# BOOT_JTAG_AUX.net
KiCad netlist of a schematic drawn in Altium Designer
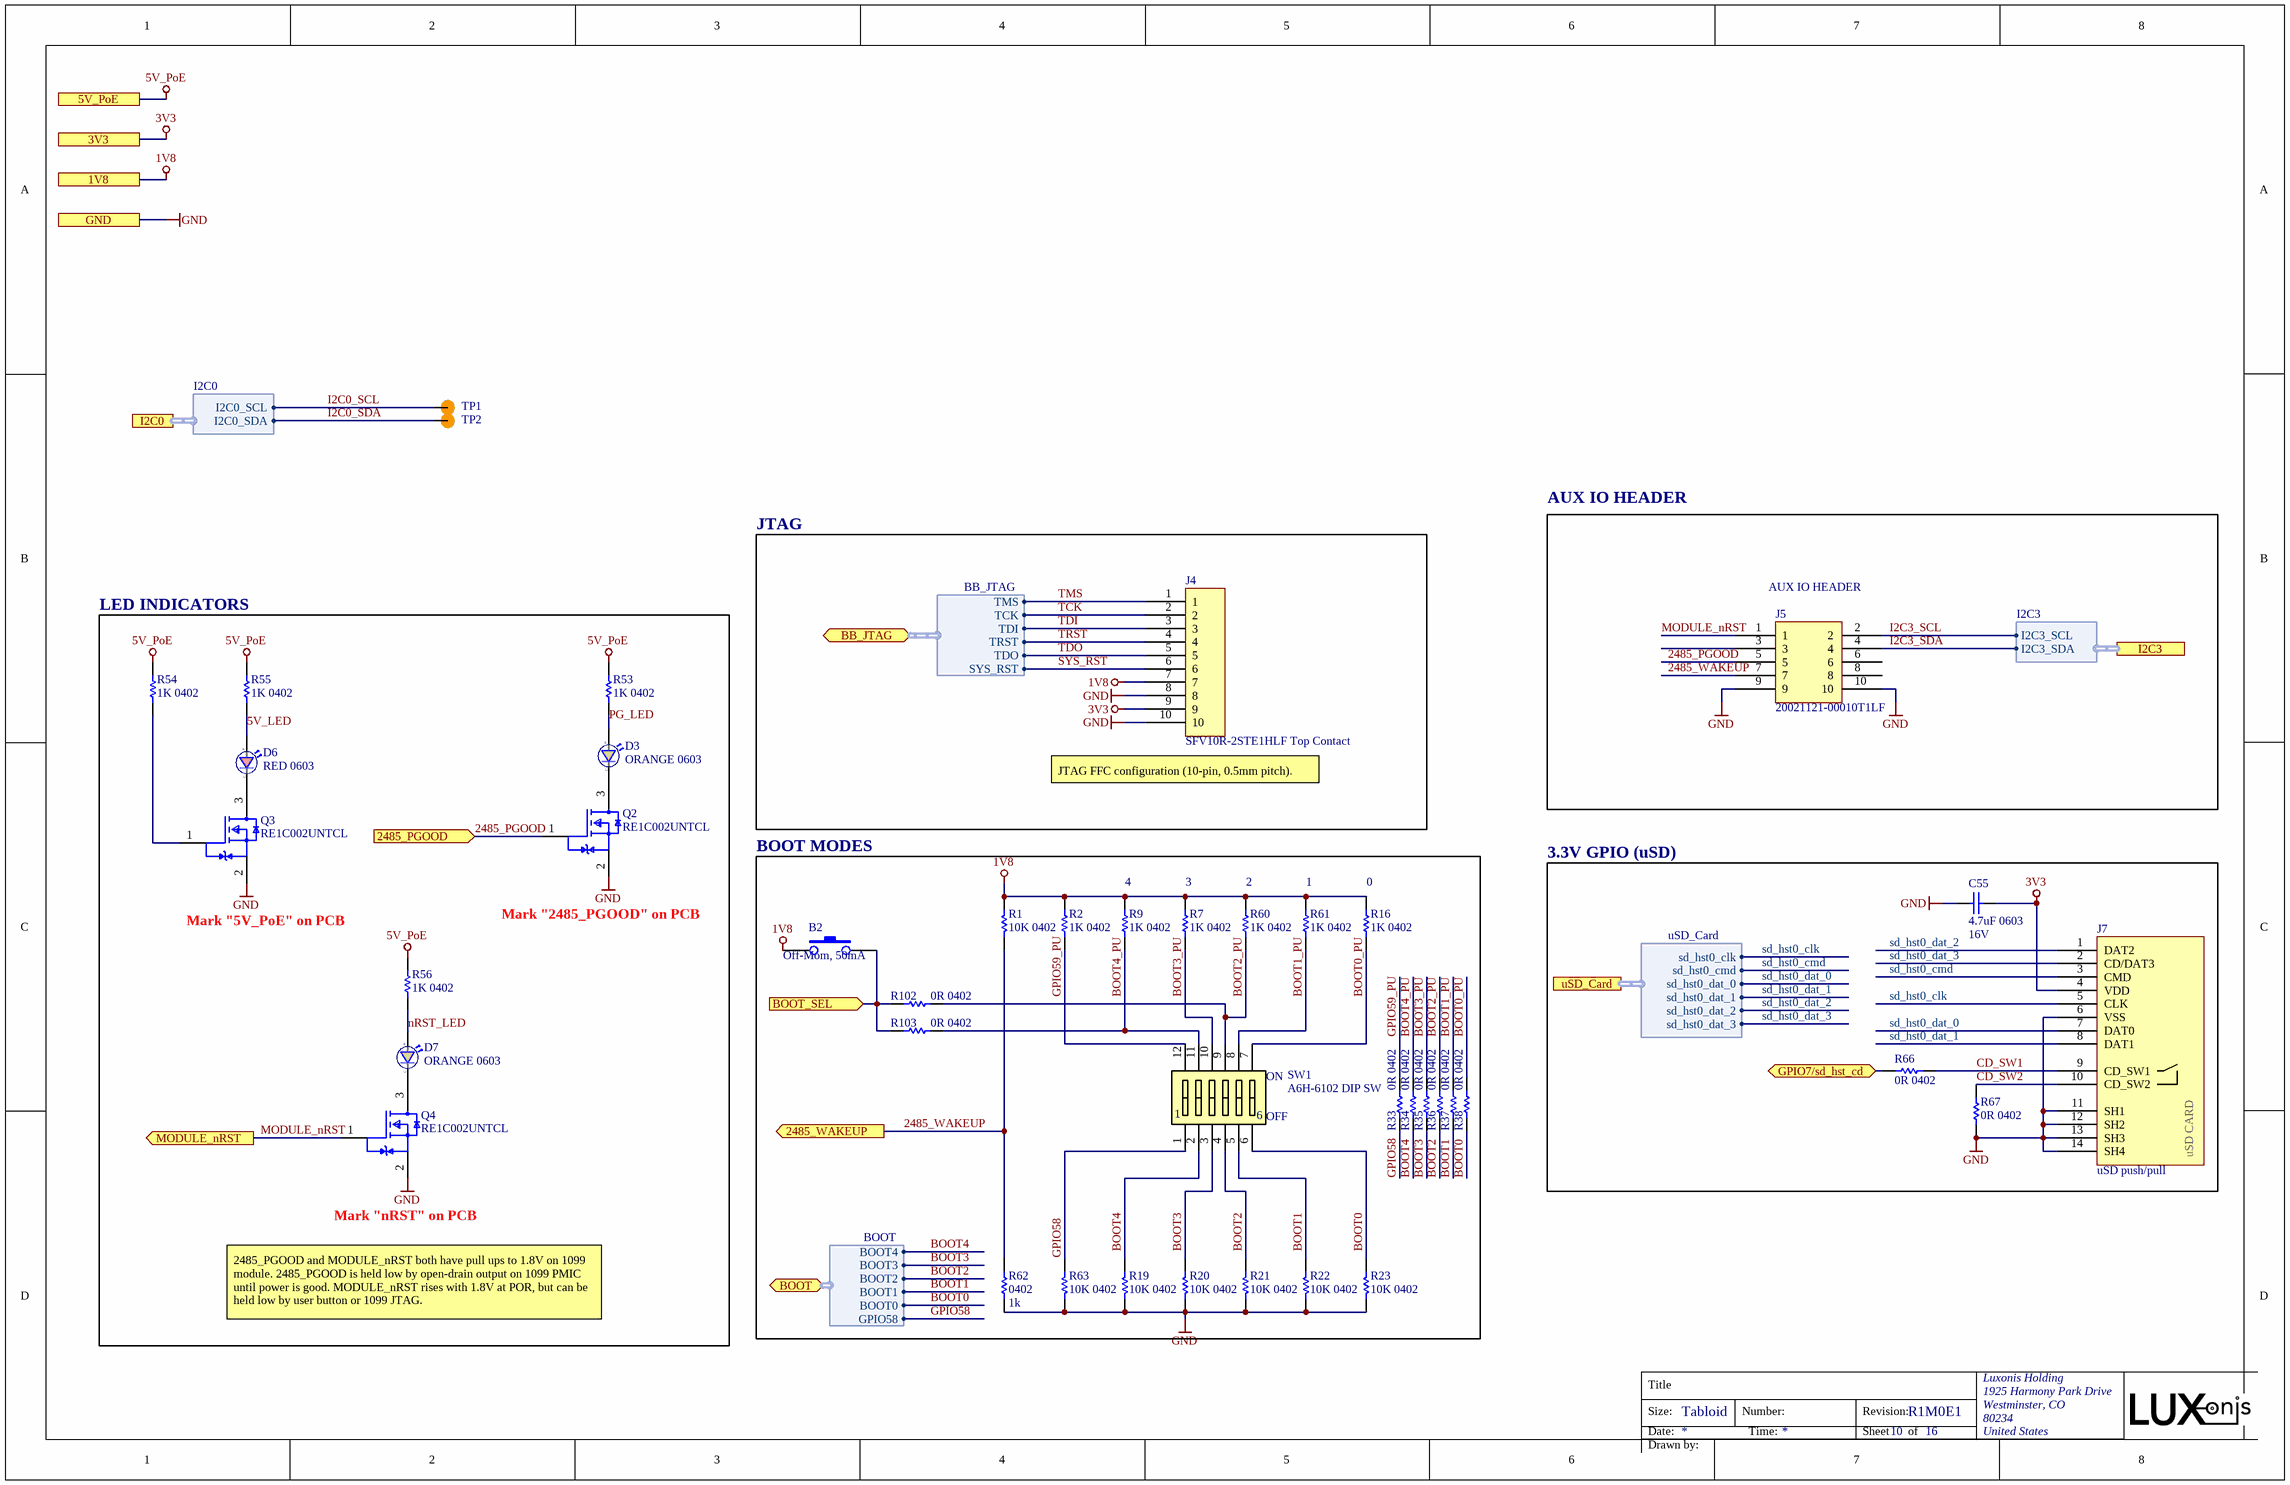
[diagram p0: BOOT_JTAG_AUX.SchDoc]

(export (version "E")
  (design (tool "Eeschema 10.0.6"))
  (components
    (comp (ref "B2")
      (value "Off-Mom, 50mA")
      (footprint "LuxonisMaster:DTSM-32N-V")
      (description "SWITCH TACTILE SMT 3.5mm * 6mm , brown 160gf")
      (libsource (lib "LuxonisMaster") (part "DTSM-32N-V"))
    )
    (comp (ref "C55")
      (value "4.7uF 0603")
      (footprint "CAPC0603(1608)100_N")
      (description "CAP CER 4.7UF 16V X5R 0603 10%")
      (fields (field (name "TOLERANCE") "10%") (field (name "VOLTAGE RATING") "16V"))
      (libsource (lib "LuxonisMaster") (part "GRM188R61C475KAAJD"))
    )
    (comp (ref "D3")
      (value "ORANGE 0603")
      (footprint "LuxonisMaster:SML_D1xx8W")
      (description "LED ORANGE DIFFUSED 0603 SMD Orange 605nm LED Indication - Discrete 2.2V 0603 (1608 Metric)")
      (libsource (lib "LuxonisMaster") (part "SML-D12D8WT86"))
    )
    (comp (ref "D6")
      (value "RED 0603")
      (footprint "LuxonisMaster:SML_D1xx8W")
      (description "LED RED DIFFUSED 0603 SMD Red 620nm LED Indication - Discrete 2.2V 0603 (1608 Metric)")
      (libsource (lib "LuxonisMaster") (part "SML-D12U8WT86"))
    )
    (comp (ref "D7")
      (value "ORANGE 0603")
      (footprint "LuxonisMaster:SML_D1xx8W")
      (description "LED ORANGE DIFFUSED 0603 SMD Orange 605nm LED Indication - Discrete 2.2V 0603 (1608 Metric)")
      (libsource (lib "LuxonisMaster") (part "SML-D12D8WT86"))
    )
    (comp (ref "J4")
      (value "SFV10R-2STE1HLF Top Contact")
      (footprint "LuxonisMaster:SFV10R-2STE1HLF")
      (description "CONN FFC TOP 10POS 0.50MM R/A")
      (libsource (lib "LuxonisMaster") (part "SFV10R-2STE1HLF"))
    )
    (comp (ref "J5")
      (value "20021121-00010T1LF")
      (footprint "LuxonisMaster:20021121-00010T1LF")
      (description "CONN HEADER SMD 10POS 1.27MM")
      (libsource (lib "LuxonisMaster") (part "20021121-00010T1LF"))
    )
    (comp (ref "J7")
      (value "uSD push/pull")
      (footprint "LuxonisMaster:104031-0811")
      (description "CONN MICRO SD CARD PUSH-PULL R/A")
      (libsource (lib "LuxonisMaster") (part "104031-0811"))
    )
    (comp (ref "Q2")
      (value "RE1C002UNTCL")
      (footprint "LuxonisMaster:RE1C002UNTCL")
      (description "MOSFET N-CH 20V 0.2A EMT3")
      (libsource (lib "LuxonisMaster") (part "RE1C002UNTCL"))
    )
    (comp (ref "Q3")
      (value "RE1C002UNTCL")
      (footprint "LuxonisMaster:RE1C002UNTCL")
      (description "MOSFET N-CH 20V 0.2A EMT3")
      (libsource (lib "LuxonisMaster") (part "RE1C002UNTCL"))
    )
    (comp (ref "Q4")
      (value "RE1C002UNTCL")
      (footprint "LuxonisMaster:RE1C002UNTCL")
      (description "MOSFET N-CH 20V 0.2A EMT3")
      (libsource (lib "LuxonisMaster") (part "RE1C002UNTCL"))
    )
    (comp (ref "R1")
      (value "10K 0402")
      (footprint "RESC0402(1005)_N")
      (fields (field (name "TOLERANCE") "1%"))
      (libsource (lib "LuxonisMaster") (part "RC0402FR-1310KL"))
    )
    (comp (ref "R2")
      (value "1K 0402")
      (footprint "RESC0402(1005)_N")
      (fields (field (name "TOLERANCE") "1%"))
      (libsource (lib "LuxonisMaster") (part "RC0402FR-071KL"))
    )
    (comp (ref "R7")
      (value "1K 0402")
      (footprint "RESC0402(1005)_N")
      (fields (field (name "TOLERANCE") "1%"))
      (libsource (lib "LuxonisMaster") (part "RC0402FR-071KL"))
    )
    (comp (ref "R9")
      (value "1K 0402")
      (footprint "RESC0402(1005)_N")
      (fields (field (name "TOLERANCE") "1%"))
      (libsource (lib "LuxonisMaster") (part "RC0402FR-071KL"))
    )
    (comp (ref "R16")
      (value "1K 0402")
      (footprint "RESC0402(1005)_N")
      (fields (field (name "TOLERANCE") "1%"))
      (libsource (lib "LuxonisMaster") (part "RC0402FR-071KL"))
    )
    (comp (ref "R19")
      (value "10K 0402")
      (footprint "RESC0402(1005)_N")
      (fields (field (name "TOLERANCE") "1%"))
      (libsource (lib "LuxonisMaster") (part "RC0402FR-1310KL"))
    )
    (comp (ref "R20")
      (value "10K 0402")
      (footprint "RESC0402(1005)_N")
      (fields (field (name "TOLERANCE") "1%"))
      (libsource (lib "LuxonisMaster") (part "RC0402FR-1310KL"))
    )
    (comp (ref "R21")
      (value "10K 0402")
      (footprint "RESC0402(1005)_N")
      (fields (field (name "TOLERANCE") "1%"))
      (libsource (lib "LuxonisMaster") (part "RC0402FR-1310KL"))
    )
    (comp (ref "R22")
      (value "10K 0402")
      (footprint "RESC0402(1005)_N")
      (fields (field (name "TOLERANCE") "1%"))
      (libsource (lib "LuxonisMaster") (part "RC0402FR-1310KL"))
    )
    (comp (ref "R23")
      (value "10K 0402")
      (footprint "RESC0402(1005)_N")
      (fields (field (name "TOLERANCE") "1%"))
      (libsource (lib "LuxonisMaster") (part "RC0402FR-1310KL"))
    )
    (comp (ref "R33")
      (value "0R 0402")
      (footprint "RES_Altium_Vault_Generic:RESC0402(1005)_L")
      (description "RES SMD 0 OHM JUMPER 1/16W 0402")
      (fields (field (name "TOLERANCE") "5%"))
      (libsource (lib "LuxonisMaster") (part "CRCW04020000Z0ED"))
    )
    (comp (ref "R34")
      (value "0R 0402")
      (footprint "RES_Altium_Vault_Generic:RESC0402(1005)_L")
      (description "RES SMD 0 OHM JUMPER 1/16W 0402")
      (fields (field (name "TOLERANCE") "5%"))
      (libsource (lib "LuxonisMaster") (part "CRCW04020000Z0ED"))
    )
    (comp (ref "R35")
      (value "0R 0402")
      (footprint "RES_Altium_Vault_Generic:RESC0402(1005)_L")
      (description "RES SMD 0 OHM JUMPER 1/16W 0402")
      (fields (field (name "TOLERANCE") "5%"))
      (libsource (lib "LuxonisMaster") (part "CRCW04020000Z0ED"))
    )
    (comp (ref "R36")
      (value "0R 0402")
      (footprint "RES_Altium_Vault_Generic:RESC0402(1005)_L")
      (description "RES SMD 0 OHM JUMPER 1/16W 0402")
      (fields (field (name "TOLERANCE") "5%"))
      (libsource (lib "LuxonisMaster") (part "CRCW04020000Z0ED"))
    )
    (comp (ref "R37")
      (value "0R 0402")
      (footprint "RES_Altium_Vault_Generic:RESC0402(1005)_L")
      (description "RES SMD 0 OHM JUMPER 1/16W 0402")
      (fields (field (name "TOLERANCE") "5%"))
      (libsource (lib "LuxonisMaster") (part "CRCW04020000Z0ED"))
    )
    (comp (ref "R38")
      (value "0R 0402")
      (footprint "RES_Altium_Vault_Generic:RESC0402(1005)_L")
      (description "RES SMD 0 OHM JUMPER 1/16W 0402")
      (fields (field (name "TOLERANCE") "5%"))
      (libsource (lib "LuxonisMaster") (part "CRCW04020000Z0ED"))
    )
    (comp (ref "R53")
      (value "1K 0402")
      (footprint "RESC0402(1005)_N")
      (fields (field (name "TOLERANCE") "1%"))
      (libsource (lib "LuxonisMaster") (part "RC0402FR-071KL"))
    )
    (comp (ref "R54")
      (value "1K 0402")
      (footprint "RESC0402(1005)_N")
      (fields (field (name "TOLERANCE") "1%"))
      (libsource (lib "LuxonisMaster") (part "RC0402FR-071KL"))
    )
    (comp (ref "R55")
      (value "1K 0402")
      (footprint "RESC0402(1005)_N")
      (fields (field (name "TOLERANCE") "1%"))
      (libsource (lib "LuxonisMaster") (part "RC0402FR-071KL"))
    )
    (comp (ref "R56")
      (value "1K 0402")
      (footprint "RESC0402(1005)_N")
      (fields (field (name "TOLERANCE") "1%"))
      (libsource (lib "LuxonisMaster") (part "RC0402FR-071KL"))
    )
    (comp (ref "R60")
      (value "1K 0402")
      (footprint "RESC0402(1005)_N")
      (fields (field (name "TOLERANCE") "1%"))
      (libsource (lib "LuxonisMaster") (part "RC0402FR-071KL"))
    )
    (comp (ref "R61")
      (value "1K 0402")
      (footprint "RESC0402(1005)_N")
      (fields (field (name "TOLERANCE") "1%"))
      (libsource (lib "LuxonisMaster") (part "RC0402FR-071KL"))
    )
    (comp (ref "R62")
      (value "1k")
      (footprint "RESC0402(1005)_L")
      (description "RES SMD 1K OHM 1% 1/16W 0402")
      (fields
        (field (name "CASE/PACKAGE") "0402")
        (field (name "TOLERANCE") "1%")
        (field (name "Comment") "RC0402FR-071KL")
      )
      (libsource (lib "Luxonis LLC") (part "Default resistor symbol"))
    )
    (comp (ref "R63")
      (value "10K 0402")
      (footprint "RESC0402(1005)_N")
      (fields (field (name "TOLERANCE") "1%"))
      (libsource (lib "LuxonisMaster") (part "RC0402FR-1310KL"))
    )
    (comp (ref "R66")
      (value "0R 0402")
      (footprint "RESC0402(1005)_N")
      (description "RES SMD 0 OHM JUMPER 1/16W 0402")
      (fields (field (name "TOLERANCE") "5%"))
      (libsource (lib "LuxonisMaster") (part "CRCW04020000Z0ED"))
    )
    (comp (ref "R67")
      (value "0R 0402")
      (footprint "RESC0402(1005)_N")
      (description "RES SMD 0 OHM JUMPER 1/16W 0402")
      (fields (field (name "TOLERANCE") "5%"))
      (libsource (lib "LuxonisMaster") (part "CRCW04020000Z0ED"))
    )
    (comp (ref "R102")
      (value "0R 0402")
      (footprint "RES_Altium_Vault_Generic:RESC0402(1005)_L")
      (description "RES SMD 0 OHM JUMPER 1/16W 0402")
      (fields (field (name "TOLERANCE") "5%"))
      (libsource (lib "LuxonisMaster") (part "CRCW04020000Z0ED"))
    )
    (comp (ref "R103")
      (value "0R 0402")
      (footprint "RES_Altium_Vault_Generic:RESC0402(1005)_L")
      (description "RES SMD 0 OHM JUMPER 1/16W 0402")
      (fields (field (name "TOLERANCE") "5%"))
      (libsource (lib "LuxonisMaster") (part "CRCW04020000Z0ED"))
    )
    (comp (ref "SW1")
      (value "A6H-6102 DIP SW")
      (footprint "LuxonisMaster:A6H-610x")
      (description "SWITCH SLIDE DIP SPST 25MA 24V (SEALED)")
      (libsource (lib "LuxonisMaster") (part "A6H-6102"))
    )
    (comp (ref "TP1")
      (value "TP100_200_NS")
      (footprint "TP100_200_NS")
      (libsource (lib "LuxonisMaster") (part "TEST_POINT"))
    )
    (comp (ref "TP2")
      (value "TP100_200_NS")
      (footprint "TP100_200_NS")
      (libsource (lib "LuxonisMaster") (part "TEST_POINT"))
    )
  )
  (nets
    (net (code "6") (name "/5V_LED") (class "Default")
      (node (ref "D6") (pin "2") (pinfunction "A_2") (pintype "passive"))
      (node (ref "R55") (pin "1") (pinfunction "1_1") (pintype "passive"))
    )
    (net (code "7") (name "/2485_PGOOD") (class "Default")
      (node (ref "J5") (pin "5") (pinfunction "5_5") (pintype "passive"))
      (node (ref "Q2") (pin "1") (pinfunction "Gate_1") (pintype "passive"))
    )
    (net (code "8") (name "/2485_WAKEUP") (class "Default")
      (node (ref "J5") (pin "7") (pinfunction "7_7") (pintype "passive"))
      (node (ref "R1") (pin "2") (pinfunction "2_2") (pintype "passive"))
      (node (ref "R62") (pin "2") (pinfunction "2_2") (pintype "passive"))
    )
    (net (code "9") (name "/BOOT0") (class "Default")
      (node (ref "R23") (pin "1") (pinfunction "1_1") (pintype "passive"))
      (node (ref "R38") (pin "2") (pinfunction "2_2") (pintype "passive"))
      (node (ref "SW1") (pin "6") (pinfunction "6_6") (pintype "passive"))
    )
    (net (code "10") (name "/BOOT0_PU") (class "Default")
      (node (ref "R16") (pin "1") (pinfunction "1_1") (pintype "passive"))
      (node (ref "R38") (pin "1") (pinfunction "1_1") (pintype "passive"))
      (node (ref "SW1") (pin "7") (pinfunction "7_7") (pintype "passive"))
    )
    (net (code "11") (name "/BOOT1") (class "Default")
      (node (ref "R22") (pin "1") (pinfunction "1_1") (pintype "passive"))
      (node (ref "R37") (pin "2") (pinfunction "2_2") (pintype "passive"))
      (node (ref "SW1") (pin "5") (pinfunction "5_5") (pintype "passive"))
    )
    (net (code "12") (name "/BOOT1_PU") (class "Default")
      (node (ref "R37") (pin "1") (pinfunction "1_1") (pintype "passive"))
      (node (ref "R61") (pin "1") (pinfunction "1_1") (pintype "passive"))
      (node (ref "SW1") (pin "8") (pinfunction "8_8") (pintype "passive"))
    )
    (net (code "13") (name "/BOOT2") (class "Default")
      (node (ref "R21") (pin "1") (pinfunction "1_1") (pintype "passive"))
      (node (ref "R36") (pin "2") (pinfunction "2_2") (pintype "passive"))
      (node (ref "SW1") (pin "4") (pinfunction "4_4") (pintype "passive"))
    )
    (net (code "14") (name "/BOOT2_PU") (class "Default")
      (node (ref "R102") (pin "1") (pinfunction "1_1") (pintype "passive"))
      (node (ref "R36") (pin "1") (pinfunction "1_1") (pintype "passive"))
      (node (ref "R60") (pin "1") (pinfunction "1_1") (pintype "passive"))
      (node (ref "SW1") (pin "9") (pinfunction "9_9") (pintype "passive"))
    )
    (net (code "15") (name "/BOOT3") (class "Default")
      (node (ref "R20") (pin "1") (pinfunction "1_1") (pintype "passive"))
      (node (ref "R35") (pin "2") (pinfunction "2_2") (pintype "passive"))
      (node (ref "SW1") (pin "3") (pinfunction "3_3") (pintype "passive"))
    )
    (net (code "16") (name "/BOOT3_PU") (class "Default")
      (node (ref "R35") (pin "1") (pinfunction "1_1") (pintype "passive"))
      (node (ref "R7") (pin "1") (pinfunction "1_1") (pintype "passive"))
      (node (ref "SW1") (pin "10") (pinfunction "10_10") (pintype "passive"))
    )
    (net (code "17") (name "/BOOT4") (class "Default")
      (node (ref "R19") (pin "1") (pinfunction "1_1") (pintype "passive"))
      (node (ref "R34") (pin "2") (pinfunction "2_2") (pintype "passive"))
      (node (ref "SW1") (pin "2") (pinfunction "2_2") (pintype "passive"))
    )
    (net (code "18") (name "/BOOT4_PU") (class "Default")
      (node (ref "R103") (pin "1") (pinfunction "1_1") (pintype "passive"))
      (node (ref "R34") (pin "1") (pinfunction "1_1") (pintype "passive"))
      (node (ref "R9") (pin "1") (pinfunction "1_1") (pintype "passive"))
      (node (ref "SW1") (pin "11") (pinfunction "11_11") (pintype "passive"))
    )
    (net (code "19") (name "/BOOT_SEL") (class "Default")
      (node (ref "B2") (pin "2") (pinfunction "2_2") (pintype "passive"))
      (node (ref "R102") (pin "2") (pinfunction "2_2") (pintype "passive"))
      (node (ref "R103") (pin "2") (pinfunction "2_2") (pintype "passive"))
    )
    (net (code "20") (name "/CD_SW1") (class "Default")
      (node (ref "J7") (pin "9") (pinfunction "CD_SW1_9") (pintype "passive"))
      (node (ref "R66") (pin "1") (pinfunction "1_1") (pintype "passive"))
    )
    (net (code "21") (name "/CD_SW2") (class "Default")
      (node (ref "J7") (pin "10") (pinfunction "CD_SW2_10") (pintype "passive"))
      (node (ref "R67") (pin "2") (pinfunction "2_2") (pintype "passive"))
    )
    (net (code "22") (name "/GPIO7{slash}sd_hst_cd") (class "Default")
      (node (ref "R66") (pin "2") (pinfunction "2_2") (pintype "passive"))
    )
    (net (code "23") (name "/GPIO58") (class "Default")
      (node (ref "R33") (pin "2") (pinfunction "2_2") (pintype "passive"))
      (node (ref "R63") (pin "1") (pinfunction "1_1") (pintype "passive"))
      (node (ref "SW1") (pin "1") (pinfunction "1_1") (pintype "passive"))
    )
    (net (code "24") (name "/GPIO59_PU") (class "Default")
      (node (ref "R2") (pin "1") (pinfunction "1_1") (pintype "passive"))
      (node (ref "R33") (pin "1") (pinfunction "1_1") (pintype "passive"))
      (node (ref "SW1") (pin "12") (pinfunction "12_12") (pintype "passive"))
    )
    (net (code "25") (name "/I2C0_SCL") (class "Default") (node (ref "TP1") (pin "1") (pintype "passive")))
    (net (code "26") (name "/I2C0_SDA") (class "Default") (node (ref "TP2") (pin "1") (pintype "passive")))
    (net (code "27") (name "/I2C3_SCL") (class "Default")
      (node (ref "J5") (pin "2") (pinfunction "2_2") (pintype "passive"))
    )
    (net (code "28") (name "/I2C3_SDA") (class "Default")
      (node (ref "J5") (pin "4") (pinfunction "4_4") (pintype "passive"))
    )
    (net (code "29") (name "/MODULE_nRST") (class "Default")
      (node (ref "J5") (pin "1") (pinfunction "1_1") (pintype "passive"))
      (node (ref "Q4") (pin "1") (pinfunction "Gate_1") (pintype "passive"))
    )
    (net (code "30") (name "/PG_LED") (class "Default")
      (node (ref "D3") (pin "2") (pinfunction "A_2") (pintype "passive"))
      (node (ref "R53") (pin "1") (pinfunction "1_1") (pintype "passive"))
    )
    (net (code "31") (name "/SYS_RST") (class "Default")
      (node (ref "J4") (pin "6") (pinfunction "6_6") (pintype "passive"))
    )
    (net (code "32") (name "/TCK") (class "Default")
      (node (ref "J4") (pin "2") (pinfunction "2_2") (pintype "passive"))
    )
    (net (code "33") (name "/TDI") (class "Default")
      (node (ref "J4") (pin "3") (pinfunction "3_3") (pintype "passive"))
    )
    (net (code "34") (name "/TDO") (class "Default")
      (node (ref "J4") (pin "5") (pinfunction "5_5") (pintype "passive"))
    )
    (net (code "35") (name "/TMS") (class "Default")
      (node (ref "J4") (pin "1") (pinfunction "1_1") (pintype "passive"))
    )
    (net (code "36") (name "/TRST") (class "Default")
      (node (ref "J4") (pin "4") (pinfunction "4_4") (pintype "passive"))
    )
    (net (code "37") (name "/nRST_LED") (class "Default")
      (node (ref "D7") (pin "2") (pinfunction "A_2") (pintype "passive"))
      (node (ref "R56") (pin "1") (pinfunction "1_1") (pintype "passive"))
    )
    (net (code "38") (name "/sd_hst0_clk") (class "Default")
      (node (ref "J7") (pin "5") (pinfunction "CLK_5") (pintype "passive"))
    )
    (net (code "39") (name "/sd_hst0_cmd") (class "Default")
      (node (ref "J7") (pin "3") (pinfunction "CMD_3") (pintype "passive"))
    )
    (net (code "40") (name "/sd_hst0_dat_0") (class "Default")
      (node (ref "J7") (pin "7") (pinfunction "DAT0_7") (pintype "passive"))
    )
    (net (code "41") (name "/sd_hst0_dat_1") (class "Default")
      (node (ref "J7") (pin "8") (pinfunction "DAT1_8") (pintype "passive"))
    )
    (net (code "42") (name "/sd_hst0_dat_2") (class "Default")
      (node (ref "J7") (pin "1") (pinfunction "DAT2_1") (pintype "passive"))
    )
    (net (code "43") (name "/sd_hst0_dat_3") (class "Default")
      (node (ref "J7") (pin "2") (pinfunction "CD/DAT3_2") (pintype "passive"))
    )
    (net (code "49") (name "1V8") (class "Default")
      (node (ref "B2") (pin "1") (pinfunction "1_1") (pintype "passive"))
      (node (ref "J4") (pin "7") (pinfunction "7_7") (pintype "passive"))
      (node (ref "R1") (pin "1") (pinfunction "1_1") (pintype "passive"))
      (node (ref "R16") (pin "2") (pinfunction "2_2") (pintype "passive"))
      (node (ref "R2") (pin "2") (pinfunction "2_2") (pintype "passive"))
      (node (ref "R60") (pin "2") (pinfunction "2_2") (pintype "passive"))
      (node (ref "R61") (pin "2") (pinfunction "2_2") (pintype "passive"))
      (node (ref "R7") (pin "2") (pinfunction "2_2") (pintype "passive"))
      (node (ref "R9") (pin "2") (pinfunction "2_2") (pintype "passive"))
    )
    (net (code "50") (name "3V3") (class "Default")
      (node (ref "C55") (pin "2") (pinfunction "2_2") (pintype "passive"))
      (node (ref "J4") (pin "9") (pinfunction "9_9") (pintype "passive"))
      (node (ref "J7") (pin "4") (pinfunction "VDD_4") (pintype "passive"))
    )
    (net (code "51") (name "5V_PoE") (class "Default")
      (node (ref "R53") (pin "2") (pinfunction "2_2") (pintype "passive"))
      (node (ref "R54") (pin "2") (pinfunction "2_2") (pintype "passive"))
      (node (ref "R55") (pin "2") (pinfunction "2_2") (pintype "passive"))
      (node (ref "R56") (pin "2") (pinfunction "2_2") (pintype "passive"))
    )
    (net (code "52") (name "GND") (class "Default")
      (node (ref "C55") (pin "1") (pinfunction "1_1") (pintype "passive"))
      (node (ref "J4") (pin "10") (pinfunction "10_10") (pintype "passive"))
      (node (ref "J4") (pin "8") (pinfunction "8_8") (pintype "passive"))
      (node (ref "J5") (pin "10") (pinfunction "10_10") (pintype "passive"))
      (node (ref "J5") (pin "9") (pinfunction "9_9") (pintype "passive"))
      (node (ref "J7") (pin "11") (pinfunction "SH1_11") (pintype "passive"))
      (node (ref "J7") (pin "12") (pinfunction "SH2_12") (pintype "passive"))
      (node (ref "J7") (pin "13") (pinfunction "SH3_13") (pintype "passive"))
      (node (ref "J7") (pin "14") (pinfunction "SH4_14") (pintype "passive"))
      (node (ref "J7") (pin "6") (pinfunction "VSS_6") (pintype "passive"))
      (node (ref "Q2") (pin "2") (pinfunction "Source_2") (pintype "passive"))
      (node (ref "Q3") (pin "2") (pinfunction "Source_2") (pintype "passive"))
      (node (ref "Q4") (pin "2") (pinfunction "Source_2") (pintype "passive"))
      (node (ref "R19") (pin "2") (pinfunction "2_2") (pintype "passive"))
      (node (ref "R20") (pin "2") (pinfunction "2_2") (pintype "passive"))
      (node (ref "R21") (pin "2") (pinfunction "2_2") (pintype "passive"))
      (node (ref "R22") (pin "2") (pinfunction "2_2") (pintype "passive"))
      (node (ref "R23") (pin "2") (pinfunction "2_2") (pintype "passive"))
      (node (ref "R62") (pin "1") (pinfunction "1_1") (pintype "passive"))
      (node (ref "R63") (pin "2") (pinfunction "2_2") (pintype "passive"))
      (node (ref "R67") (pin "1") (pinfunction "1_1") (pintype "passive"))
    )
    (net (code "53") (name "Net-(D3-C)") (class "Default")
      (node (ref "D3") (pin "1") (pinfunction "C_1") (pintype "passive"))
      (node (ref "Q2") (pin "3") (pinfunction "Drain_3") (pintype "passive"))
    )
    (net (code "54") (name "Net-(D6-C)") (class "Default")
      (node (ref "D6") (pin "1") (pinfunction "C_1") (pintype "passive"))
      (node (ref "Q3") (pin "3") (pinfunction "Drain_3") (pintype "passive"))
    )
    (net (code "55") (name "Net-(D7-C)") (class "Default")
      (node (ref "D7") (pin "1") (pinfunction "C_1") (pintype "passive"))
      (node (ref "Q4") (pin "3") (pinfunction "Drain_3") (pintype "passive"))
    )
    (net (code "56") (name "Net-(Q3-Gate)") (class "Default")
      (node (ref "Q3") (pin "1") (pinfunction "Gate_1") (pintype "passive"))
      (node (ref "R54") (pin "1") (pinfunction "1_1") (pintype "passive"))
    )
    (net (code "57") (name "unconnected-(J5-Pad3)") (class "Default")
      (node (ref "J5") (pin "3") (pinfunction "3_3") (pintype "passive"))
    )
    (net (code "58") (name "unconnected-(J5-Pad6)") (class "Default")
      (node (ref "J5") (pin "6") (pinfunction "6_6") (pintype "passive"))
    )
    (net (code "59") (name "unconnected-(J5-Pad8)") (class "Default")
      (node (ref "J5") (pin "8") (pinfunction "8_8") (pintype "passive"))
    )
  )
)
